# TCAN1146_PWR_MGMT.net
KiCad netlist of a schematic drawn in Altium Designer
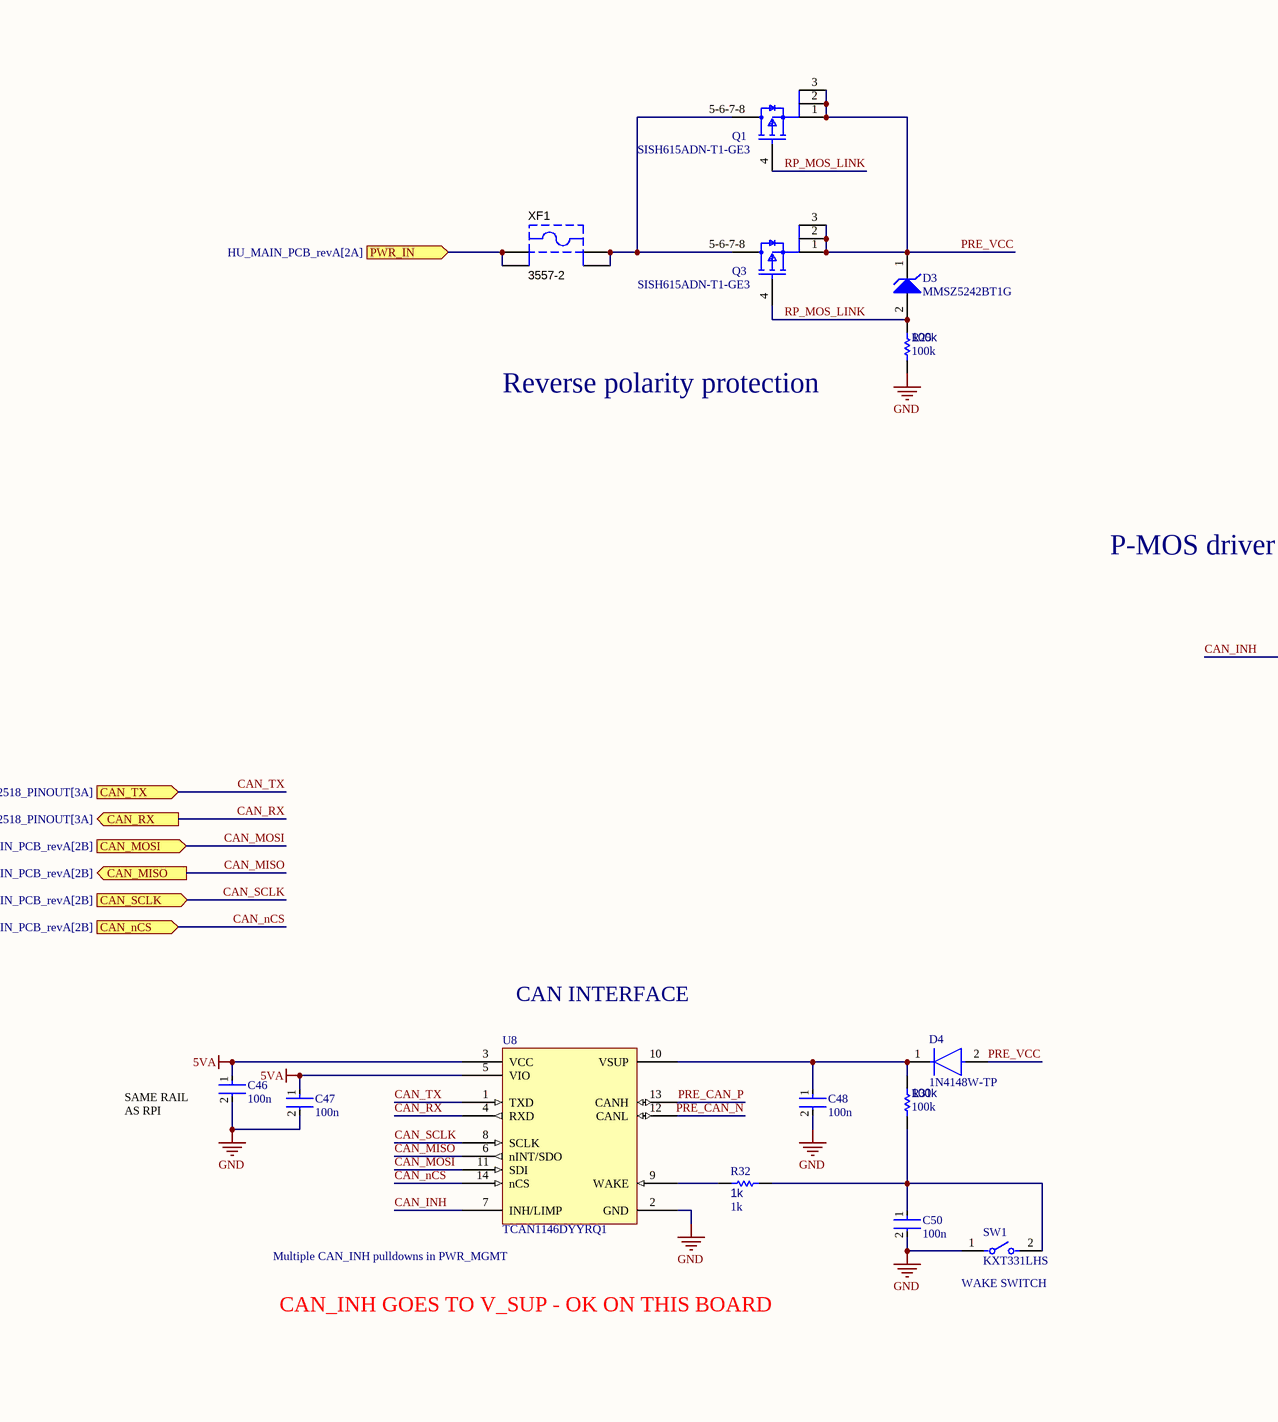
[diagram p0: TCAN1146_PWR_MGMT.SchDoc, left]
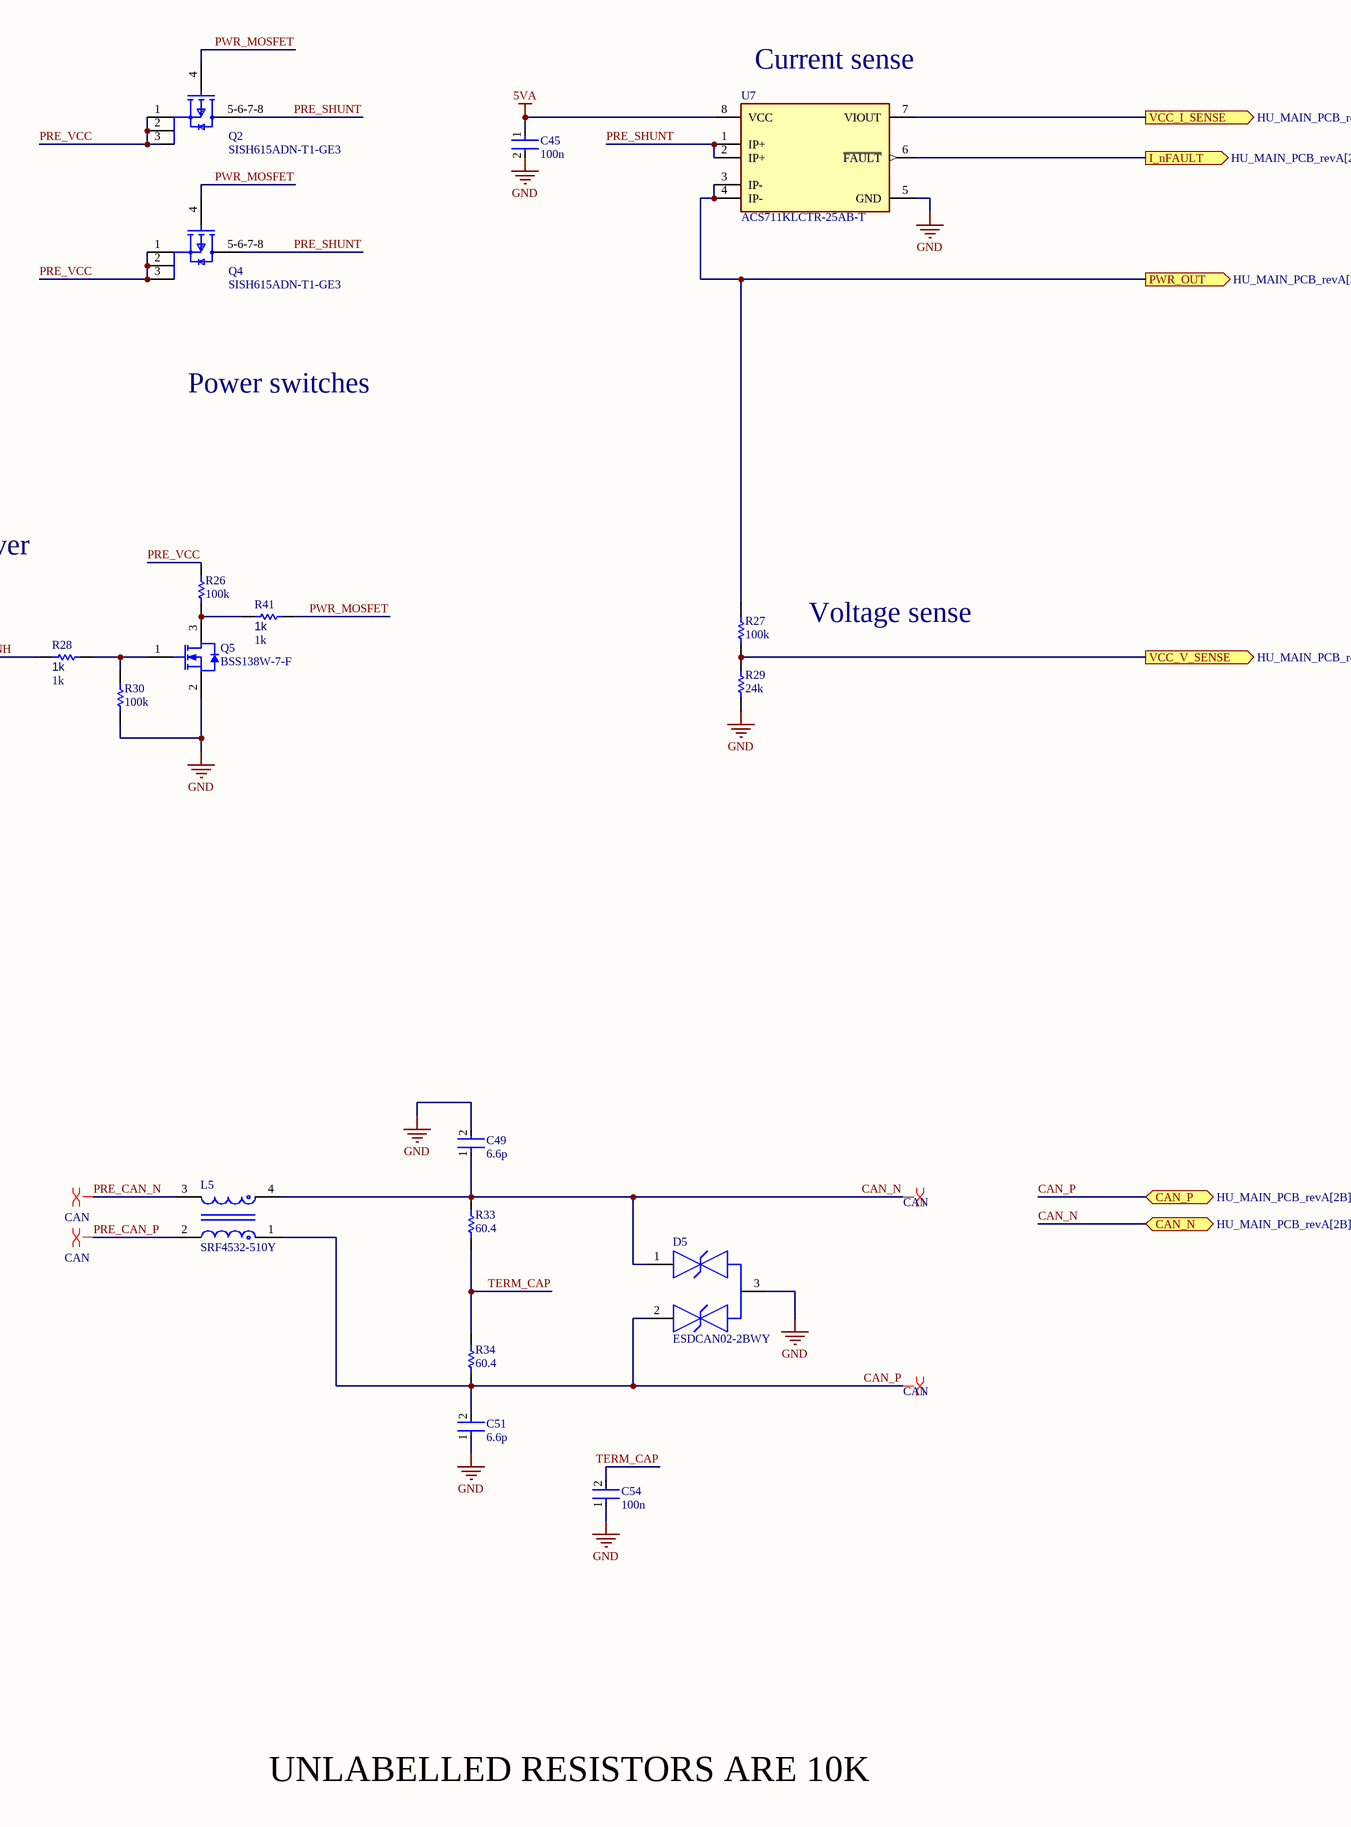
[diagram p1: TCAN1146_PWR_MGMT.SchDoc, right]

(export (version "E")
  (design (tool "Eeschema 10.0.6"))
  (components
    (comp (ref "C45")
      (value "100n")
      (footprint "FP-0402-L_1_0_0_05-W_0_5-IPC_A")
      (description "LARGE PADS, 0402 CAP, CHANGE COMMENT TO MATCH REAL P/N")
      (libsource (lib "Space Concordia") (part "b4654b650e69147ec39a6b967a45e02"))
    )
    (comp (ref "C46")
      (value "100n")
      (footprint "FP-0402-L_1_0_0_05-W_0_5-IPC_A")
      (description "LARGE PADS, 0402 CAP, CHANGE COMMENT TO MATCH REAL P/N")
      (libsource (lib "Space Concordia") (part "b4654b650e69147ec39a6b967a45e02"))
    )
    (comp (ref "C47")
      (value "100n")
      (footprint "FP-0402-L_1_0_0_05-W_0_5-IPC_A")
      (description "LARGE PADS, 0402 CAP, CHANGE COMMENT TO MATCH REAL P/N")
      (libsource (lib "Space Concordia") (part "b4654b650e69147ec39a6b967a45e02"))
    )
    (comp (ref "C48")
      (value "100n")
      (footprint "FP-0402-L_1_0_0_05-W_0_5-IPC_A")
      (description "LARGE PADS, 0402 CAP, CHANGE COMMENT TO MATCH REAL P/N")
      (libsource (lib "Space Concordia") (part "b4654b650e69147ec39a6b967a45e02"))
    )
    (comp (ref "C49")
      (value "6.6p")
      (footprint "FP-0402-L_1_0_0_05-W_0_5-IPC_A")
      (description "LARGE PADS, 0402 CAP, CHANGE COMMENT TO MATCH REAL P/N")
      (libsource (lib "Space Concordia") (part "b4654b650e69147ec39a6b967a45e02"))
    )
    (comp (ref "C50")
      (value "100n")
      (footprint "FP-0402-L_1_0_0_05-W_0_5-IPC_A")
      (description "LARGE PADS, 0402 CAP, CHANGE COMMENT TO MATCH REAL P/N")
      (libsource (lib "Space Concordia") (part "b4654b650e69147ec39a6b967a45e02"))
    )
    (comp (ref "C51")
      (value "6.6p")
      (footprint "FP-0402-L_1_0_0_05-W_0_5-IPC_A")
      (description "LARGE PADS, 0402 CAP, CHANGE COMMENT TO MATCH REAL P/N")
      (libsource (lib "Space Concordia") (part "b4654b650e69147ec39a6b967a45e02"))
    )
    (comp (ref "C54")
      (value "100n")
      (footprint "FP-0402-L_1_0_0_05-W_0_5-IPC_A")
      (description "LARGE PADS, 0402 CAP, CHANGE COMMENT TO MATCH REAL P/N")
      (libsource (lib "Space Concordia") (part "b4654b650e69147ec39a6b967a45e02"))
    )
    (comp (ref "D3")
      (value "MMSZ5242BT1G")
      (footprint "ONSC-SOD-123-2-425-04_V")
      (description "Zener Voltage Regulator, 500 mW, 2-Pin SOD-123, Pb-Free, Tape and Reel")
      (fields (field (name "MANUFACTURER") "On Semiconductor"))
      (libsource (lib "Altium Content Vault") (part "ONSC-K1A2-2"))
    )
    (comp (ref "D4")
      (value "1N4148W-TP")
      (footprint "FP-SOD-123-IPC_A")
      (description "DIODE GEN PURP 100V 150MA SOD123")
      (libsource (lib "Altium Content Vault") (part "d7152d700b627762746794eb795d46e"))
    )
    (comp (ref "D5")
      (value "ESDCAN02-2BWY")
      (footprint "FP-SOT323-3L-MFG")
      (description "TVS DIODE 26.5V 44V SOT323-3")
      (fields
        (field (name "MANUFACTURER") "STMicroelectronics")
        (field (name "OCTOPART") "https://octopart.com/esdcan02-2bwy-stmicroelectronics-58631133")
      )
      (libsource (lib "Altium Content Vault") (part "0b9019fb5e52ed66df21ec1535be59d"))
    )
    (comp (ref "L5")
      (value "SRF4532-510Y")
      (footprint "FP-SRF4532-MFG")
      (description "CMC 51UH 200MA 2LN 2KOHM SMD")
      (fields (field (name "TOLERANCE") "50%"))
      (libsource (lib "Altium Content Vault") (part "aca3f6a10b859f211cca95010157f3b"))
    )
    (comp (ref "Q1")
      (value "SISH615ADN-T1-GE3")
      (footprint "SISH615ADN-T1-GE3-Footprint-1")
      (description "Trans MOSFET P-CH 20V 22.1A 8-Pin PowerPAK 1212 EP T/R")
      (libsource (lib "Space Concordia") (part "CMP-013-00036-4"))
    )
    (comp (ref "Q2")
      (value "SISH615ADN-T1-GE3")
      (footprint "SISH615ADN-T1-GE3-Footprint-1")
      (description "Trans MOSFET P-CH 20V 22.1A 8-Pin PowerPAK 1212 EP T/R")
      (libsource (lib "Space Concordia") (part "CMP-013-00036-4"))
    )
    (comp (ref "Q3")
      (value "SISH615ADN-T1-GE3")
      (footprint "SISH615ADN-T1-GE3-Footprint-1")
      (description "Trans MOSFET P-CH 20V 22.1A 8-Pin PowerPAK 1212 EP T/R")
      (libsource (lib "Space Concordia") (part "CMP-013-00036-4"))
    )
    (comp (ref "Q4")
      (value "SISH615ADN-T1-GE3")
      (footprint "SISH615ADN-T1-GE3-Footprint-1")
      (description "Trans MOSFET P-CH 20V 22.1A 8-Pin PowerPAK 1212 EP T/R")
      (libsource (lib "Space Concordia") (part "CMP-013-00036-4"))
    )
    (comp (ref "Q5")
      (value "BSS138W-7-F")
      (footprint "DIOD-SOT323-3_V")
      (fields (field (name "MANUFACTURER") "DiodesIncorporated"))
      (libsource (lib "Altium Content Vault") (part "NEMOS-GSD-3"))
    )
    (comp (ref "R25")
      (value "100k")
      (footprint "R0603B")
      (description "Resistor")
      (fields (field (name "ALTIUM_VALUE") "100k"))
      (libsource (lib "Space Concordia") (part "Resistor"))
    )
    (comp (ref "R26")
      (value "100k")
      (footprint "R0603B")
      (description "Resistor")
      (libsource (lib "Space Concordia") (part "Resistor"))
    )
    (comp (ref "R27")
      (value "100k")
      (footprint "R0603B")
      (description "Resistor")
      (libsource (lib "Space Concordia") (part "Resistor"))
    )
    (comp (ref "R28")
      (value "1k")
      (footprint "R0603B")
      (description "Resistor")
      (fields (field (name "ALTIUM_VALUE") "1k"))
      (libsource (lib "Space Concordia") (part "Resistor"))
    )
    (comp (ref "R29")
      (value "24k")
      (footprint "R0603B")
      (description "Resistor")
      (libsource (lib "Space Concordia") (part "Resistor"))
    )
    (comp (ref "R30")
      (value "100k")
      (footprint "R0603B")
      (description "Resistor")
      (libsource (lib "Space Concordia") (part "Resistor"))
    )
    (comp (ref "R31")
      (value "100k")
      (footprint "R0603B")
      (description "Resistor")
      (fields (field (name "ALTIUM_VALUE") "100k"))
      (libsource (lib "Space Concordia") (part "Resistor"))
    )
    (comp (ref "R32")
      (value "1k")
      (footprint "R0603B")
      (description "Resistor")
      (fields (field (name "ALTIUM_VALUE") "1k"))
      (libsource (lib "Space Concordia") (part "Resistor"))
    )
    (comp (ref "R33")
      (value "60.4")
      (footprint "R0603B")
      (description "Resistor")
      (libsource (lib "Space Concordia") (part "Resistor"))
    )
    (comp (ref "R34")
      (value "60.4")
      (footprint "R0603B")
      (description "Resistor")
      (libsource (lib "Space Concordia") (part "Resistor"))
    )
    (comp (ref "R41")
      (value "1k")
      (footprint "R0603B")
      (description "Resistor")
      (fields (field (name "ALTIUM_VALUE") "1k"))
      (libsource (lib "Space Concordia") (part "Resistor"))
    )
    (comp (ref "SW1")
      (value "KXT331LHS")
      (footprint "FP-KXT331LHS-MFG")
      (description "SWITCH TACTILE SPST-NO 0.02A 15V")
      (libsource (lib "Altium Content Vault") (part "bb27bde45df87f1f469753f287ef5ae"))
    )
    (comp (ref "U7")
      (value "ACS711KLCTR-25AB-T")
      (footprint "FP-LC-8-IPC_A")
      (description "SENSOR CURRENT HALL 25A AC/DC")
      (libsource (lib "Altium Content Vault") (part "eeba3158841281b4ae542a6e24976ab"))
    )
    (comp (ref "U8")
      (value "TCAN1146DYYRQ1")
      (footprint "TCAN1146DYYRQ1-Footprint-1")
      (libsource (lib "Space Concordia") (part "CMP-015-00012-2"))
    )
    (comp (ref "XF1")
      (value "3557-2")
      (footprint "KSTN-3557-2")
      (description "FUSE HOLDER, PCB MOUNT, 500VAC, 20A, ROHS")
      (fields (field (name "VOLTAGE") "500V") (field (name "MANUFACTURER") "Keystone-Electronics"))
      (libsource (lib "Altium Content Vault") (part "FUSE_HOLDER-4"))
    )
  )
  (nets
    (net (code "1") (name "/CAN_INH") (class "Default")
      (node (ref "R28") (pin "1") (pinfunction "1_1") (pintype "passive"))
      (node (ref "U8") (pin "7") (pinfunction "INH/LIMP_7") (pintype "passive"))
    )
    (net (code "2") (name "/CAN_MISO") (class "Default")
      (node (ref "U8") (pin "6") (pinfunction "nINT/SDO_6") (pintype "output"))
    )
    (net (code "3") (name "/CAN_MOSI") (class "Default")
      (node (ref "U8") (pin "11") (pinfunction "SDI_11") (pintype "input"))
    )
    (net (code "4") (name "/CAN_N") (class "Default")
      (node (ref "C49") (pin "1") (pinfunction "1_1") (pintype "passive"))
      (node (ref "D5") (pin "1") (pinfunction "1_1") (pintype "passive"))
      (node (ref "L5") (pin "4") (pinfunction "4_4") (pintype "passive"))
      (node (ref "R33") (pin "2") (pinfunction "2_2") (pintype "passive"))
    )
    (net (code "5") (name "/CAN_P") (class "Default")
      (node (ref "C51") (pin "2") (pinfunction "2_2") (pintype "passive"))
      (node (ref "D5") (pin "2") (pinfunction "2_2") (pintype "passive"))
      (node (ref "L5") (pin "1") (pinfunction "1_1") (pintype "passive"))
      (node (ref "R34") (pin "1") (pinfunction "1_1") (pintype "passive"))
    )
    (net (code "6") (name "/CAN_RX") (class "Default")
      (node (ref "U8") (pin "4") (pinfunction "RXD_4") (pintype "output"))
    )
    (net (code "7") (name "/CAN_SCLK") (class "Default")
      (node (ref "U8") (pin "8") (pinfunction "SCLK_8") (pintype "input"))
    )
    (net (code "8") (name "/CAN_TX") (class "Default")
      (node (ref "U8") (pin "1") (pinfunction "TXD_1") (pintype "input"))
    )
    (net (code "9") (name "/CAN_nCS") (class "Default")
      (node (ref "U8") (pin "14") (pinfunction "nCS_14") (pintype "input"))
    )
    (net (code "10") (name "/I_nFAULT") (class "Default")
      (node (ref "U7") (pin "6") (pinfunction "~{FAULT}_6") (pintype "output"))
    )
    (net (code "11") (name "/PRE_CAN_N") (class "Default")
      (node (ref "L5") (pin "3") (pinfunction "3_3") (pintype "passive"))
      (node (ref "U8") (pin "12") (pinfunction "CANL_12") (pintype "bidirectional"))
    )
    (net (code "12") (name "/PRE_CAN_P") (class "Default")
      (node (ref "L5") (pin "2") (pinfunction "2_2") (pintype "passive"))
      (node (ref "U8") (pin "13") (pinfunction "CANH_13") (pintype "bidirectional"))
    )
    (net (code "13") (name "/PRE_SHUNT") (class "Default")
      (node (ref "Q2") (pin "5-6-7-8") (pinfunction "D_5-6-7-8") (pintype "passive"))
      (node (ref "Q4") (pin "5-6-7-8") (pinfunction "D_5-6-7-8") (pintype "passive"))
      (node (ref "U7") (pin "1") (pinfunction "IP+_1") (pintype "passive"))
      (node (ref "U7") (pin "2") (pinfunction "IP+_2") (pintype "passive"))
    )
    (net (code "14") (name "/PRE_VCC") (class "Default")
      (node (ref "D3") (pin "1") (pinfunction "K_1") (pintype "passive"))
      (node (ref "D4") (pin "2") (pinfunction "A_2") (pintype "passive"))
      (node (ref "Q1") (pin "1") (pinfunction "S_1") (pintype "passive"))
      (node (ref "Q1") (pin "2") (pinfunction "S_2") (pintype "passive"))
      (node (ref "Q1") (pin "3") (pinfunction "S_3") (pintype "passive"))
      (node (ref "Q2") (pin "1") (pinfunction "S_1") (pintype "passive"))
      (node (ref "Q2") (pin "2") (pinfunction "S_2") (pintype "passive"))
      (node (ref "Q2") (pin "3") (pinfunction "S_3") (pintype "passive"))
      (node (ref "Q3") (pin "1") (pinfunction "S_1") (pintype "passive"))
      (node (ref "Q3") (pin "2") (pinfunction "S_2") (pintype "passive"))
      (node (ref "Q3") (pin "3") (pinfunction "S_3") (pintype "passive"))
      (node (ref "Q4") (pin "1") (pinfunction "S_1") (pintype "passive"))
      (node (ref "Q4") (pin "2") (pinfunction "S_2") (pintype "passive"))
      (node (ref "Q4") (pin "3") (pinfunction "S_3") (pintype "passive"))
      (node (ref "R26") (pin "2") (pinfunction "2_2") (pintype "passive"))
    )
    (net (code "15") (name "/PWR_IN") (class "Default")
      (node (ref "XF1") (pin "1") (pinfunction "1_1") (pintype "passive"))
      (node (ref "XF1") (pin "2") (pinfunction "2_2") (pintype "passive"))
    )
    (net (code "16") (name "/PWR_MOSFET") (class "Default")
      (node (ref "Q2") (pin "4") (pinfunction "G_4") (pintype "passive"))
      (node (ref "Q4") (pin "4") (pinfunction "G_4") (pintype "passive"))
      (node (ref "R41") (pin "2") (pinfunction "2_2") (pintype "passive"))
    )
    (net (code "17") (name "/PWR_OUT") (class "Default")
      (node (ref "R27") (pin "2") (pinfunction "2_2") (pintype "passive"))
      (node (ref "U7") (pin "3") (pinfunction "IP-_3") (pintype "passive"))
      (node (ref "U7") (pin "4") (pinfunction "IP-_4") (pintype "passive"))
    )
    (net (code "18") (name "/RP_MOS_LINK") (class "Default")
      (node (ref "D3") (pin "2") (pinfunction "A_2") (pintype "passive"))
      (node (ref "Q1") (pin "4") (pinfunction "G_4") (pintype "passive"))
      (node (ref "Q3") (pin "4") (pinfunction "G_4") (pintype "passive"))
      (node (ref "R25") (pin "2") (pinfunction "2_2") (pintype "passive"))
    )
    (net (code "19") (name "/TERM_CAP") (class "Default")
      (node (ref "C54") (pin "2") (pinfunction "2_2") (pintype "passive"))
      (node (ref "R33") (pin "1") (pinfunction "1_1") (pintype "passive"))
      (node (ref "R34") (pin "2") (pinfunction "2_2") (pintype "passive"))
    )
    (net (code "20") (name "/VCC_I_SENSE") (class "Default")
      (node (ref "U7") (pin "7") (pinfunction "VIOUT_7") (pintype "passive"))
    )
    (net (code "21") (name "/VCC_V_SENSE") (class "Default")
      (node (ref "R27") (pin "1") (pinfunction "1_1") (pintype "passive"))
      (node (ref "R29") (pin "2") (pinfunction "2_2") (pintype "passive"))
    )
    (net (code "22") (name "5VA") (class "Default")
      (node (ref "C45") (pin "1") (pinfunction "1_1") (pintype "passive"))
      (node (ref "C46") (pin "1") (pinfunction "1_1") (pintype "passive"))
      (node (ref "C47") (pin "1") (pinfunction "1_1") (pintype "passive"))
      (node (ref "U7") (pin "8") (pinfunction "VCC_8") (pintype "power_in"))
      (node (ref "U8") (pin "3") (pinfunction "VCC_3") (pintype "power_in"))
      (node (ref "U8") (pin "5") (pinfunction "VIO_5") (pintype "power_in"))
    )
    (net (code "23") (name "GND") (class "Default")
      (node (ref "C45") (pin "2") (pinfunction "2_2") (pintype "passive"))
      (node (ref "C46") (pin "2") (pinfunction "2_2") (pintype "passive"))
      (node (ref "C47") (pin "2") (pinfunction "2_2") (pintype "passive"))
      (node (ref "C48") (pin "2") (pinfunction "2_2") (pintype "passive"))
      (node (ref "C49") (pin "2") (pinfunction "2_2") (pintype "passive"))
      (node (ref "C50") (pin "2") (pinfunction "2_2") (pintype "passive"))
      (node (ref "C51") (pin "1") (pinfunction "1_1") (pintype "passive"))
      (node (ref "C54") (pin "1") (pinfunction "1_1") (pintype "passive"))
      (node (ref "D5") (pin "3") (pinfunction "3_3") (pintype "passive"))
      (node (ref "Q5") (pin "2") (pinfunction "S_2") (pintype "passive"))
      (node (ref "R25") (pin "1") (pinfunction "1_1") (pintype "passive"))
      (node (ref "R29") (pin "1") (pinfunction "1_1") (pintype "passive"))
      (node (ref "R30") (pin "1") (pinfunction "1_1") (pintype "passive"))
      (node (ref "SW1") (pin "1") (pinfunction "1_1") (pintype "passive"))
      (node (ref "U7") (pin "5") (pinfunction "GND_5") (pintype "power_in"))
      (node (ref "U8") (pin "2") (pinfunction "GND_2") (pintype "power_in"))
    )
    (net (code "24") (name "Net-(C50-Pad1)") (class "Default")
      (node (ref "C50") (pin "1") (pinfunction "1_1") (pintype "passive"))
      (node (ref "R31") (pin "1") (pinfunction "1_1") (pintype "passive"))
      (node (ref "R32") (pin "2") (pinfunction "2_2") (pintype "passive"))
      (node (ref "SW1") (pin "2") (pinfunction "2_2") (pintype "passive"))
    )
    (net (code "25") (name "Net-(D4-C)") (class "Default")
      (node (ref "C48") (pin "1") (pinfunction "1_1") (pintype "passive"))
      (node (ref "D4") (pin "1") (pinfunction "C_1") (pintype "passive"))
      (node (ref "R31") (pin "2") (pinfunction "2_2") (pintype "passive"))
      (node (ref "U8") (pin "10") (pinfunction "VSUP_10") (pintype "power_in"))
    )
    (net (code "26") (name "Net-(Q1-D)") (class "Default")
      (node (ref "Q1") (pin "5-6-7-8") (pinfunction "D_5-6-7-8") (pintype "passive"))
      (node (ref "Q3") (pin "5-6-7-8") (pinfunction "D_5-6-7-8") (pintype "passive"))
      (node (ref "XF1") (pin "3") (pinfunction "3_3") (pintype "passive"))
      (node (ref "XF1") (pin "4") (pinfunction "4_4") (pintype "passive"))
    )
    (net (code "27") (name "Net-(Q5-D)") (class "Default")
      (node (ref "Q5") (pin "3") (pinfunction "D_3") (pintype "passive"))
      (node (ref "R26") (pin "1") (pinfunction "1_1") (pintype "passive"))
      (node (ref "R41") (pin "1") (pinfunction "1_1") (pintype "passive"))
    )
    (net (code "28") (name "Net-(Q5-G)") (class "Default")
      (node (ref "Q5") (pin "1") (pinfunction "G_1") (pintype "passive"))
      (node (ref "R28") (pin "2") (pinfunction "2_2") (pintype "passive"))
      (node (ref "R30") (pin "2") (pinfunction "2_2") (pintype "passive"))
    )
    (net (code "29") (name "Net-(U8-WAKE)") (class "Default")
      (node (ref "R32") (pin "1") (pinfunction "1_1") (pintype "passive"))
      (node (ref "U8") (pin "9") (pinfunction "WAKE_9") (pintype "input"))
    )
  )
)
